# spot_check_rev_2.net
KiCad netlist of a schematic drawn in EAGLE
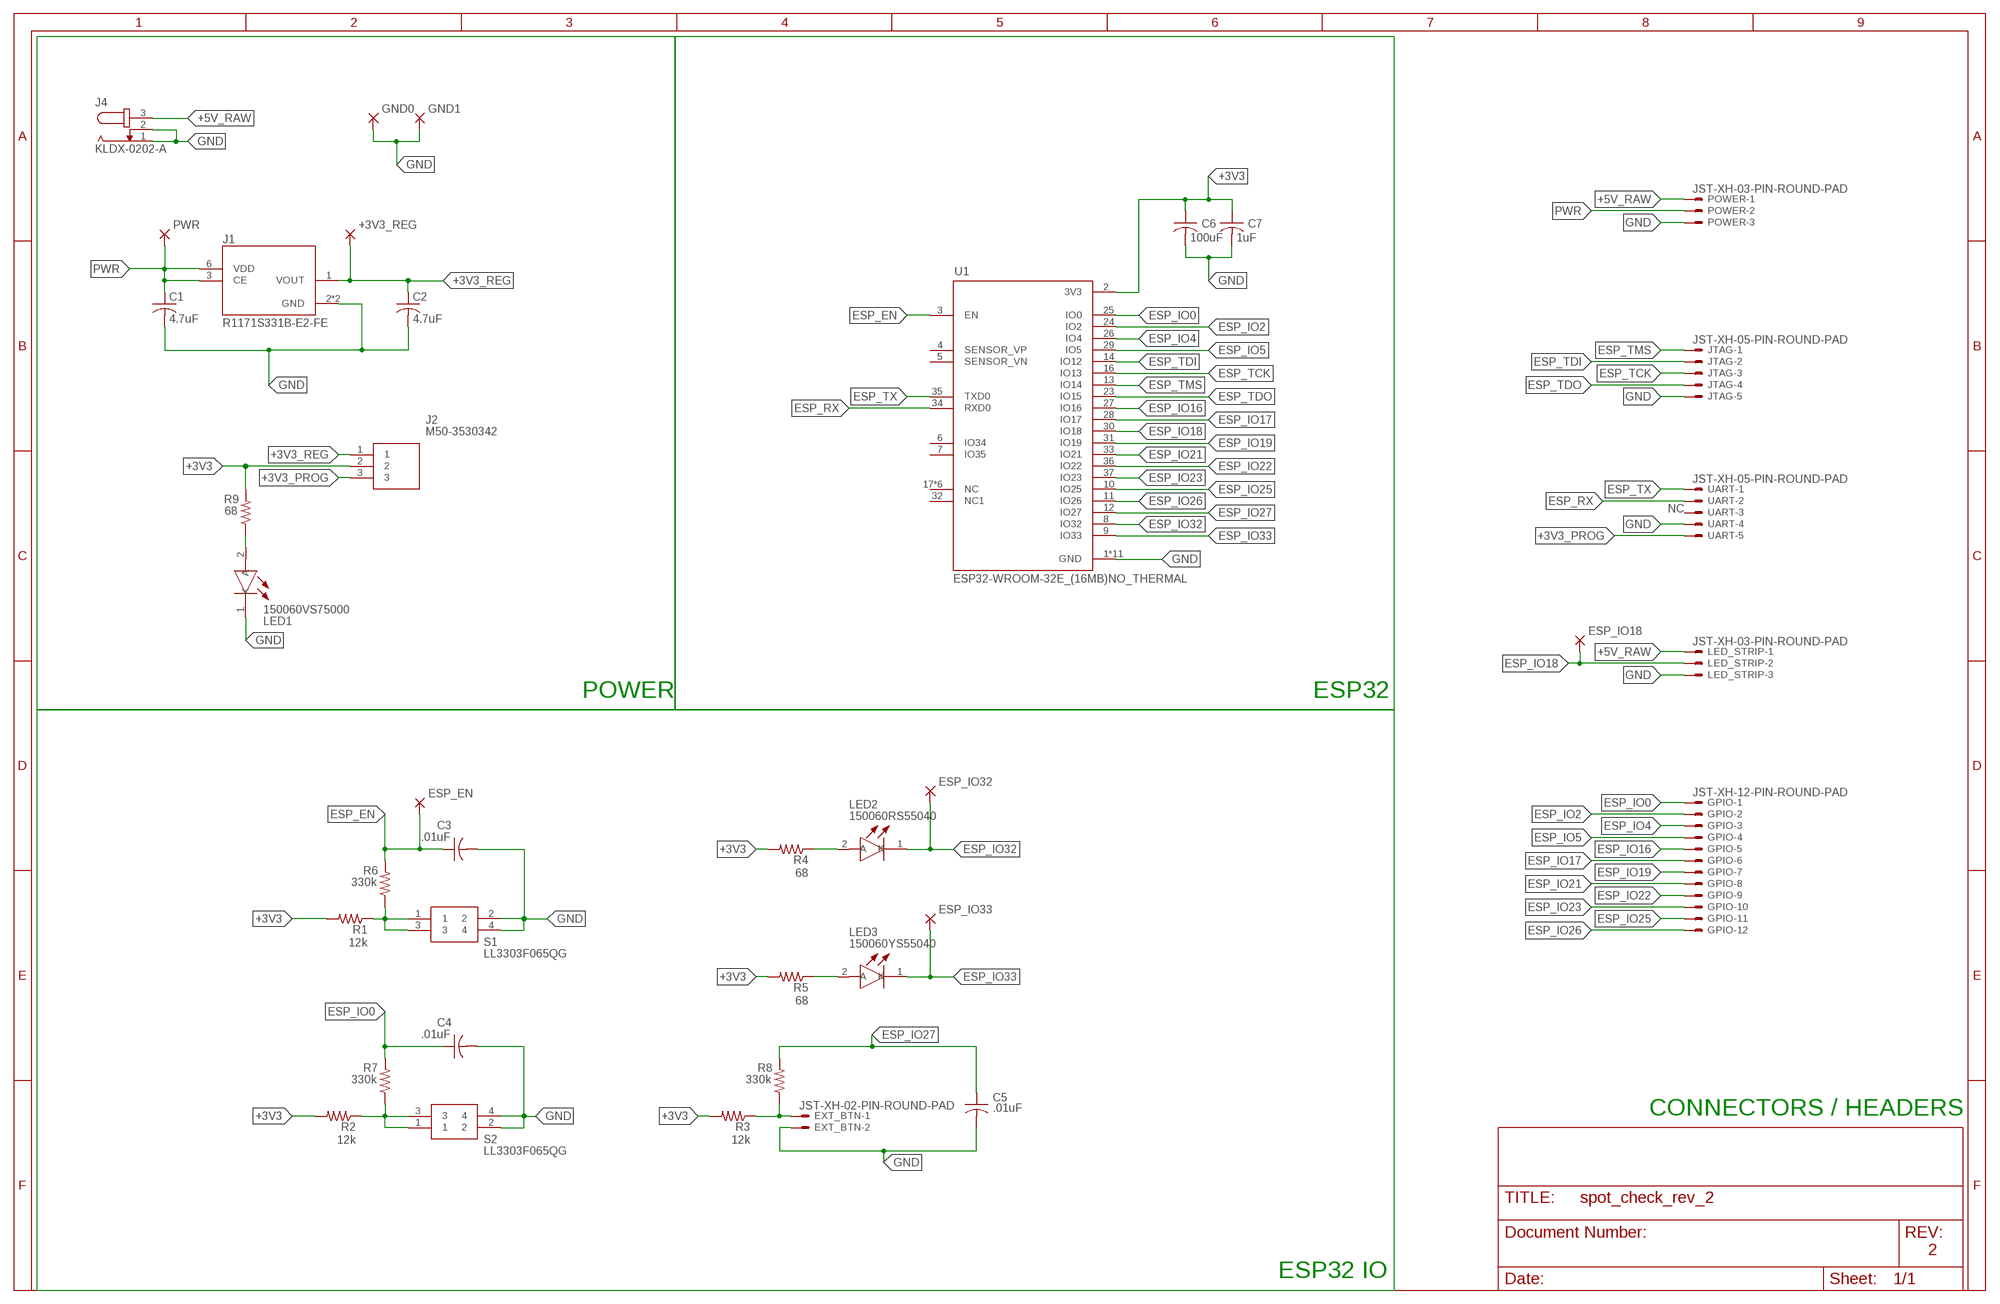
[diagram p0: schematic, sheet 1]

(export (version "E")
  (design (tool "Eeschema 10.0.6"))
  (components
    (comp (ref "+3V3_REG")
      (value "TP")
      (footprint "eagle-import:2,54_1,1")
      (libsource (lib "eagle-import") (part "2,54/1,1"))
    )
    (comp (ref "C1")
      (value "4.7uF")
      (footprint "eagle-import:C0805")
      (libsource (lib "eagle-import") (part "C-USC0805"))
    )
    (comp (ref "C2")
      (value "4.7uF")
      (footprint "eagle-import:C0805")
      (libsource (lib "eagle-import") (part "C-USC0805"))
    )
    (comp (ref "C3")
      (value ".01uF")
      (footprint "eagle-import:C0805")
      (libsource (lib "eagle-import") (part "C-USC0805"))
    )
    (comp (ref "C4")
      (value ".01uF")
      (footprint "eagle-import:C0805")
      (libsource (lib "eagle-import") (part "C-USC0805"))
    )
    (comp (ref "C5")
      (value ".01uF")
      (footprint "eagle-import:C0805")
      (libsource (lib "eagle-import") (part "C-USC0805"))
    )
    (comp (ref "C6")
      (value "100uF")
      (footprint "eagle-import:C0805")
      (libsource (lib "eagle-import") (part "C-USC0805"))
    )
    (comp (ref "C7")
      (value "1uF")
      (footprint "eagle-import:C0805")
      (libsource (lib "eagle-import") (part "C-USC0805"))
    )
    (comp (ref "ESP_EN")
      (value "TP")
      (footprint "eagle-import:2,54_1,1")
      (libsource (lib "eagle-import") (part "2,54/1,1"))
    )
    (comp (ref "ESP_IO18")
      (value "TP")
      (footprint "eagle-import:2,54_1,1")
      (libsource (lib "eagle-import") (part "2,54/1,1"))
    )
    (comp (ref "ESP_IO32")
      (value "TP")
      (footprint "eagle-import:2,54_1,1")
      (libsource (lib "eagle-import") (part "2,54/1,1"))
    )
    (comp (ref "ESP_IO33")
      (value "TP")
      (footprint "eagle-import:2,54_1,1")
      (libsource (lib "eagle-import") (part "2,54/1,1"))
    )
    (comp (ref "EXT_BTN")
      (value "JST-XH-02-PIN-ROUND-PAD")
      (footprint "eagle-import:JST-XH-02-PACKAGE-ROUND-PAD")
      (libsource (lib "eagle-import") (part "JST-XH-02-PIN-ROUND-PAD"))
    )
    (comp (ref "GND0")
      (value "TP")
      (footprint "eagle-import:2,54_1,1")
      (libsource (lib "eagle-import") (part "2,54/1,1"))
    )
    (comp (ref "GND1")
      (value "TP")
      (footprint "eagle-import:2,54_1,1")
      (libsource (lib "eagle-import") (part "2,54/1,1"))
    )
    (comp (ref "GPIO")
      (value "JST-XH-12-PIN-ROUND-PAD")
      (footprint "eagle-import:JST-XH-12-PACKAGE-ROUND-PAD")
      (libsource (lib "eagle-import") (part "JST-XH-12-PIN-ROUND-PAD"))
    )
    (comp (ref "J1")
      (value "R1171S331B-E2-FE")
      (footprint "eagle-import:REG_R1171S421B-E2-FE")
      (fields (field (name "MF") "Ricoh") (field (name "MP") "R1171S421B-E2-FE"))
      (libsource (lib "eagle-import") (part "R1171S421B-E2-FE"))
    )
    (comp (ref "J2")
      (value "M50-3530342")
      (footprint "eagle-import:HDRV3W40P0X127_1X3_381X210X430")
      (fields (field (name "MOUSER_PART_NUMBER") "855-M50-3530342"))
      (libsource (lib "eagle-import") (part "M50-3530342"))
    )
    (comp (ref "J4")
      (value "KLDX-0202-A")
      (footprint "eagle-import:SPC4077")
      (libsource (lib "eagle-import") (part "CONN-JACK"))
    )
    (comp (ref "JTAG")
      (value "JST-XH-05-PIN-ROUND-PAD")
      (footprint "eagle-import:JST-XH-05-PACKAGE-ROUND-PAD")
      (libsource (lib "eagle-import") (part "JST-XH-05-PIN-ROUND-PAD"))
    )
    (comp (ref "LED1")
      (value "150060VS75000")
      (footprint "eagle-import:LEDC1608X80N")
      (fields (field (name "MF") "Wurth Elektronik"))
      (libsource (lib "eagle-import") (part "150060VS75000"))
    )
    (comp (ref "LED2")
      (value "150060RS55040")
      (footprint "eagle-import:LEDC1608X80N")
      (fields (field (name "MF") "Wurth Elektronik") (field (name "MP") "150060VS75000"))
      (libsource (lib "eagle-import") (part "150060VS75000"))
    )
    (comp (ref "LED3")
      (value "150060YS55040")
      (footprint "eagle-import:LEDC1608X80N")
      (fields (field (name "MF") "Wurth Elektronik") (field (name "MP") "150060VS75000"))
      (libsource (lib "eagle-import") (part "150060VS75000"))
    )
    (comp (ref "LED_STRIP")
      (value "JST-XH-03-PIN-ROUND-PAD")
      (footprint "eagle-import:JST-XH-03-PACKAGE-ROUND-PAD")
      (libsource (lib "eagle-import") (part "JST-XH-03-PIN-ROUND-PAD"))
    )
    (comp (ref "POWER")
      (value "JST-XH-03-PIN-ROUND-PAD")
      (footprint "eagle-import:JST-XH-03-PACKAGE-ROUND-PAD")
      (libsource (lib "eagle-import") (part "JST-XH-03-PIN-ROUND-PAD"))
    )
    (comp (ref "PWR")
      (value "TP")
      (footprint "eagle-import:2,54_1,1")
      (libsource (lib "eagle-import") (part "2,54/1,1"))
    )
    (comp (ref "R1")
      (value "12k")
      (footprint "eagle-import:R0805")
      (libsource (lib "eagle-import") (part "R-US_R0805"))
    )
    (comp (ref "R2")
      (value "12k")
      (footprint "eagle-import:R0805")
      (libsource (lib "eagle-import") (part "R-US_R0805"))
    )
    (comp (ref "R3")
      (value "12k")
      (footprint "eagle-import:R0805")
      (libsource (lib "eagle-import") (part "R-US_R0805"))
    )
    (comp (ref "R4")
      (value "68")
      (footprint "eagle-import:R0805")
      (libsource (lib "eagle-import") (part "R-US_R0805"))
    )
    (comp (ref "R5")
      (value "68")
      (footprint "eagle-import:R0805")
      (libsource (lib "eagle-import") (part "R-US_R0805"))
    )
    (comp (ref "R6")
      (value "330k")
      (footprint "eagle-import:R0805")
      (libsource (lib "eagle-import") (part "R-US_R0805"))
    )
    (comp (ref "R7")
      (value "330k")
      (footprint "eagle-import:R0805")
      (libsource (lib "eagle-import") (part "R-US_R0805"))
    )
    (comp (ref "R8")
      (value "330k")
      (footprint "eagle-import:R0805")
      (libsource (lib "eagle-import") (part "R-US_R0805"))
    )
    (comp (ref "R9")
      (value "68")
      (footprint "eagle-import:R0805")
      (libsource (lib "eagle-import") (part "R-US_R0805"))
    )
    (comp (ref "S1")
      (value "LL3303F065QG")
      (footprint "eagle-import:LL3303F065QG")
      (fields (field (name "MOUSER_PART_NUMBER") "612-LL3303F065QG"))
      (libsource (lib "eagle-import") (part "LL3303F065QG"))
    )
    (comp (ref "S2")
      (value "LL3303F065QG")
      (footprint "eagle-import:LL3303F065QG")
      (fields (field (name "MOUSER_PART_NUMBER") "612-LL3303F065QG"))
      (libsource (lib "eagle-import") (part "LL3303F065QG"))
    )
    (comp (ref "U1")
      (value "ESP32-WROOM-32E_(16MB)NO_THERMAL")
      (footprint "eagle-import:MODULE_ESP32-WROOM-32E_(16MB)")
      (libsource (lib "eagle-import") (part "ESP32-WROOM-32E_(16MB)NO_THERMAL"))
    )
    (comp (ref "UART")
      (value "JST-XH-05-PIN-ROUND-PAD")
      (footprint "eagle-import:JST-XH-05-PACKAGE-ROUND-PAD")
      (fields (field (name "NC") "NC"))
      (libsource (lib "eagle-import") (part "JST-XH-05-PIN-ROUND-PAD"))
    )
  )
  (nets
    (net (code "1") (name "+3V3") (class "Default")
      (node (ref "C6") (pin "1") (pinfunction "1_1") (pintype "passive"))
      (node (ref "C7") (pin "1") (pinfunction "1_1") (pintype "passive"))
      (node (ref "J2") (pin "2") (pinfunction "2_2") (pintype "bidirectional"))
      (node (ref "R1") (pin "2") (pinfunction "2_2") (pintype "passive"))
      (node (ref "R2") (pin "2") (pinfunction "2_2") (pintype "passive"))
      (node (ref "R3") (pin "2") (pinfunction "2_2") (pintype "passive"))
      (node (ref "R4") (pin "2") (pinfunction "2_2") (pintype "passive"))
      (node (ref "R5") (pin "2") (pinfunction "2_2") (pintype "passive"))
      (node (ref "R9") (pin "2") (pinfunction "2_2") (pintype "passive"))
      (node (ref "U1") (pin "2") (pinfunction "3V3_2") (pintype "power_in"))
    )
    (net (code "2") (name "+3V3_PROG") (class "Default")
      (node (ref "J2") (pin "3") (pinfunction "3_3") (pintype "bidirectional"))
      (node (ref "UART") (pin "5") (pinfunction "S_5") (pintype "passive"))
    )
    (net (code "3") (name "+3V3_REG") (class "Default")
      (node (ref "+3V3_REG") (pin "1") (pinfunction "P_1") (pintype "passive"))
      (node (ref "C2") (pin "1") (pinfunction "1_1") (pintype "passive"))
      (node (ref "J1") (pin "1") (pinfunction "VOUT_1") (pintype "output"))
      (node (ref "J2") (pin "1") (pinfunction "1_1") (pintype "bidirectional"))
    )
    (net (code "4") (name "+5V_RAW") (class "Default")
      (node (ref "J4") (pin "3") (pinfunction "3_3") (pintype "passive"))
      (node (ref "LED_STRIP") (pin "1") (pinfunction "S_1") (pintype "passive"))
      (node (ref "POWER") (pin "1") (pinfunction "S_1") (pintype "passive"))
    )
    (net (code "5") (name "ESP_EN") (class "Default")
      (node (ref "C3") (pin "1") (pinfunction "1_1") (pintype "passive"))
      (node (ref "ESP_EN") (pin "1") (pinfunction "P_1") (pintype "passive"))
      (node (ref "R6") (pin "2") (pinfunction "2_2") (pintype "passive"))
      (node (ref "U1") (pin "3") (pinfunction "EN_3") (pintype "input"))
    )
    (net (code "6") (name "ESP_IO0") (class "Default")
      (node (ref "C4") (pin "1") (pinfunction "1_1") (pintype "passive"))
      (node (ref "GPIO") (pin "1") (pinfunction "S_1") (pintype "passive"))
      (node (ref "R7") (pin "2") (pinfunction "2_2") (pintype "passive"))
      (node (ref "U1") (pin "25") (pinfunction "IO0_25") (pintype "bidirectional"))
    )
    (net (code "7") (name "ESP_IO2") (class "Default")
      (node (ref "GPIO") (pin "2") (pinfunction "S_2") (pintype "passive"))
      (node (ref "U1") (pin "24") (pinfunction "IO2_24") (pintype "bidirectional"))
    )
    (net (code "8") (name "ESP_IO4") (class "Default")
      (node (ref "GPIO") (pin "3") (pinfunction "S_3") (pintype "passive"))
      (node (ref "U1") (pin "26") (pinfunction "IO4_26") (pintype "bidirectional"))
    )
    (net (code "9") (name "ESP_IO5") (class "Default")
      (node (ref "GPIO") (pin "4") (pinfunction "S_4") (pintype "passive"))
      (node (ref "U1") (pin "29") (pinfunction "IO5_29") (pintype "bidirectional"))
    )
    (net (code "10") (name "ESP_IO16") (class "Default")
      (node (ref "GPIO") (pin "5") (pinfunction "S_5") (pintype "passive"))
      (node (ref "U1") (pin "27") (pinfunction "IO16_27") (pintype "bidirectional"))
    )
    (net (code "11") (name "ESP_IO17") (class "Default")
      (node (ref "GPIO") (pin "6") (pinfunction "S_6") (pintype "passive"))
      (node (ref "U1") (pin "28") (pinfunction "IO17_28") (pintype "bidirectional"))
    )
    (net (code "12") (name "ESP_IO18") (class "Default")
      (node (ref "ESP_IO18") (pin "1") (pinfunction "P_1") (pintype "passive"))
      (node (ref "LED_STRIP") (pin "2") (pinfunction "S_2") (pintype "passive"))
      (node (ref "U1") (pin "30") (pinfunction "IO18_30") (pintype "bidirectional"))
    )
    (net (code "13") (name "ESP_IO19") (class "Default")
      (node (ref "GPIO") (pin "7") (pinfunction "S_7") (pintype "passive"))
      (node (ref "U1") (pin "31") (pinfunction "IO19_31") (pintype "bidirectional"))
    )
    (net (code "14") (name "ESP_IO21") (class "Default")
      (node (ref "GPIO") (pin "8") (pinfunction "S_8") (pintype "passive"))
      (node (ref "U1") (pin "33") (pinfunction "IO21_33") (pintype "bidirectional"))
    )
    (net (code "15") (name "ESP_IO22") (class "Default")
      (node (ref "GPIO") (pin "9") (pinfunction "S_9") (pintype "passive"))
      (node (ref "U1") (pin "36") (pinfunction "IO22_36") (pintype "bidirectional"))
    )
    (net (code "16") (name "ESP_IO23") (class "Default")
      (node (ref "GPIO") (pin "10") (pinfunction "S_10") (pintype "passive"))
      (node (ref "U1") (pin "37") (pinfunction "IO23_37") (pintype "bidirectional"))
    )
    (net (code "17") (name "ESP_IO25") (class "Default")
      (node (ref "GPIO") (pin "11") (pinfunction "S_11") (pintype "passive"))
      (node (ref "U1") (pin "10") (pinfunction "IO25_10") (pintype "bidirectional"))
    )
    (net (code "18") (name "ESP_IO26") (class "Default")
      (node (ref "GPIO") (pin "12") (pinfunction "S_12") (pintype "passive"))
      (node (ref "U1") (pin "11") (pinfunction "IO26_11") (pintype "bidirectional"))
    )
    (net (code "19") (name "ESP_IO27") (class "Default")
      (node (ref "C5") (pin "1") (pinfunction "1_1") (pintype "passive"))
      (node (ref "R8") (pin "2") (pinfunction "2_2") (pintype "passive"))
      (node (ref "U1") (pin "12") (pinfunction "IO27_12") (pintype "bidirectional"))
    )
    (net (code "20") (name "ESP_IO32") (class "Default")
      (node (ref "ESP_IO32") (pin "1") (pinfunction "P_1") (pintype "passive"))
      (node (ref "LED2") (pin "1") (pinfunction "K_1") (pintype "bidirectional"))
      (node (ref "U1") (pin "8") (pinfunction "IO32_8") (pintype "bidirectional"))
    )
    (net (code "21") (name "ESP_IO33") (class "Default")
      (node (ref "ESP_IO33") (pin "1") (pinfunction "P_1") (pintype "passive"))
      (node (ref "LED3") (pin "1") (pinfunction "K_1") (pintype "bidirectional"))
      (node (ref "U1") (pin "9") (pinfunction "IO33_9") (pintype "bidirectional"))
    )
    (net (code "22") (name "ESP_RX") (class "Default")
      (node (ref "U1") (pin "34") (pinfunction "RXD0_34") (pintype "bidirectional"))
      (node (ref "UART") (pin "2") (pinfunction "S_2") (pintype "passive"))
    )
    (net (code "23") (name "ESP_TCK") (class "Default")
      (node (ref "JTAG") (pin "3") (pinfunction "S_3") (pintype "passive"))
      (node (ref "U1") (pin "16") (pinfunction "IO13_16") (pintype "bidirectional"))
    )
    (net (code "24") (name "ESP_TDI") (class "Default")
      (node (ref "JTAG") (pin "2") (pinfunction "S_2") (pintype "passive"))
      (node (ref "U1") (pin "14") (pinfunction "IO12_14") (pintype "bidirectional"))
    )
    (net (code "25") (name "ESP_TDO") (class "Default")
      (node (ref "JTAG") (pin "4") (pinfunction "S_4") (pintype "passive"))
      (node (ref "U1") (pin "23") (pinfunction "IO15_23") (pintype "bidirectional"))
    )
    (net (code "26") (name "ESP_TMS") (class "Default")
      (node (ref "JTAG") (pin "1") (pinfunction "S_1") (pintype "passive"))
      (node (ref "U1") (pin "13") (pinfunction "IO14_13") (pintype "bidirectional"))
    )
    (net (code "27") (name "ESP_TX") (class "Default")
      (node (ref "U1") (pin "35") (pinfunction "TXD0_35") (pintype "bidirectional"))
      (node (ref "UART") (pin "1") (pinfunction "S_1") (pintype "passive"))
    )
    (net (code "28") (name "GND") (class "Default")
      (node (ref "C1") (pin "2") (pinfunction "2_2") (pintype "passive"))
      (node (ref "C2") (pin "2") (pinfunction "2_2") (pintype "passive"))
      (node (ref "C3") (pin "2") (pinfunction "2_2") (pintype "passive"))
      (node (ref "C4") (pin "2") (pinfunction "2_2") (pintype "passive"))
      (node (ref "C5") (pin "2") (pinfunction "2_2") (pintype "passive"))
      (node (ref "C6") (pin "2") (pinfunction "2_2") (pintype "passive"))
      (node (ref "C7") (pin "2") (pinfunction "2_2") (pintype "passive"))
      (node (ref "EXT_BTN") (pin "2") (pinfunction "S_2") (pintype "passive"))
      (node (ref "GND0") (pin "1") (pinfunction "P_1") (pintype "passive"))
      (node (ref "GND1") (pin "1") (pinfunction "P_1") (pintype "passive"))
      (node (ref "J1") (pin "2") (pinfunction "GND_2") (pintype "power_in"))
      (node (ref "J1") (pin "5") (pinfunction "GND_5") (pintype "power_in"))
      (node (ref "J4") (pin "1") (pinfunction "1_1") (pintype "passive"))
      (node (ref "J4") (pin "2") (pinfunction "2_2") (pintype "passive"))
      (node (ref "JTAG") (pin "5") (pinfunction "S_5") (pintype "passive"))
      (node (ref "LED1") (pin "1") (pinfunction "K_1") (pintype "bidirectional"))
      (node (ref "LED_STRIP") (pin "3") (pinfunction "S_3") (pintype "passive"))
      (node (ref "POWER") (pin "3") (pinfunction "S_3") (pintype "passive"))
      (node (ref "S1") (pin "2") (pinfunction "2_2") (pintype "bidirectional"))
      (node (ref "S1") (pin "4") (pinfunction "4_4") (pintype "bidirectional"))
      (node (ref "S2") (pin "2") (pinfunction "2_2") (pintype "bidirectional"))
      (node (ref "S2") (pin "4") (pinfunction "4_4") (pintype "bidirectional"))
      (node (ref "U1") (pin "1") (pinfunction "GND_1") (pintype "power_in"))
      (node (ref "U1") (pin "15") (pinfunction "GND_15") (pintype "power_in"))
      (node (ref "U1") (pin "38") (pinfunction "GND_38") (pintype "power_in"))
      (node (ref "U1") (pin "39_1") (pinfunction "GND_39_1") (pintype "power_in"))
      (node (ref "U1") (pin "39_13") (pinfunction "GND_39_13") (pintype "power_in"))
      (node (ref "U1") (pin "39_18") (pinfunction "GND_39_18") (pintype "power_in"))
      (node (ref "U1") (pin "39_3") (pinfunction "GND_39_3") (pintype "power_in"))
      (node (ref "U1") (pin "39_4") (pinfunction "GND_39_4") (pintype "power_in"))
      (node (ref "U1") (pin "39_6") (pinfunction "GND_39_6") (pintype "power_in"))
      (node (ref "U1") (pin "39_7") (pinfunction "GND_39_7") (pintype "power_in"))
      (node (ref "U1") (pin "39_9") (pinfunction "GND_39_9") (pintype "power_in"))
      (node (ref "UART") (pin "4") (pinfunction "S_4") (pintype "passive"))
    )
    (net (code "29") (name "Net-(EXT_BTNA-S)") (class "Default")
      (node (ref "EXT_BTN") (pin "1") (pinfunction "S_1") (pintype "passive"))
      (node (ref "R3") (pin "1") (pinfunction "1_1") (pintype "passive"))
      (node (ref "R8") (pin "1") (pinfunction "1_1") (pintype "passive"))
    )
    (net (code "30") (name "Net-(LED1-A)") (class "Default")
      (node (ref "LED1") (pin "2") (pinfunction "A_2") (pintype "bidirectional"))
      (node (ref "R9") (pin "1") (pinfunction "1_1") (pintype "passive"))
    )
    (net (code "31") (name "Net-(LED2-A)") (class "Default")
      (node (ref "LED2") (pin "2") (pinfunction "A_2") (pintype "bidirectional"))
      (node (ref "R4") (pin "1") (pinfunction "1_1") (pintype "passive"))
    )
    (net (code "32") (name "Net-(LED3-A)") (class "Default")
      (node (ref "LED3") (pin "2") (pinfunction "A_2") (pintype "bidirectional"))
      (node (ref "R5") (pin "1") (pinfunction "1_1") (pintype "passive"))
    )
    (net (code "33") (name "Net-(R1-Pad1)") (class "Default")
      (node (ref "R1") (pin "1") (pinfunction "1_1") (pintype "passive"))
      (node (ref "R6") (pin "1") (pinfunction "1_1") (pintype "passive"))
      (node (ref "S1") (pin "1") (pinfunction "1_1") (pintype "bidirectional"))
      (node (ref "S1") (pin "3") (pinfunction "3_3") (pintype "bidirectional"))
    )
    (net (code "34") (name "Net-(R2-Pad1)") (class "Default")
      (node (ref "R2") (pin "1") (pinfunction "1_1") (pintype "passive"))
      (node (ref "R7") (pin "1") (pinfunction "1_1") (pintype "passive"))
      (node (ref "S2") (pin "1") (pinfunction "1_1") (pintype "bidirectional"))
      (node (ref "S2") (pin "3") (pinfunction "3_3") (pintype "bidirectional"))
    )
    (net (code "35") (name "PWR") (class "Default")
      (node (ref "C1") (pin "1") (pinfunction "1_1") (pintype "passive"))
      (node (ref "J1") (pin "3") (pinfunction "CE_3") (pintype "input"))
      (node (ref "J1") (pin "6") (pinfunction "VDD_6") (pintype "input"))
      (node (ref "POWER") (pin "2") (pinfunction "S_2") (pintype "passive"))
      (node (ref "PWR") (pin "1") (pinfunction "P_1") (pintype "passive"))
    )
    (net (code "36") (name "unconnected-(U1-IO34-Pad6)") (class "Default")
      (node (ref "U1") (pin "6") (pinfunction "IO34_6") (pintype "input"))
    )
    (net (code "37") (name "unconnected-(U1-IO35-Pad7)") (class "Default")
      (node (ref "U1") (pin "7") (pinfunction "IO35_7") (pintype "input"))
    )
    (net (code "38") (name "unconnected-(U1-NC-Pad17)") (class "Default")
      (node (ref "U1") (pin "17") (pinfunction "NC_17") (pintype "no_connect"))
    )
    (net (code "39") (name "unconnected-(U1-NC-Pad18)") (class "Default")
      (node (ref "U1") (pin "18") (pinfunction "NC_18") (pintype "no_connect"))
    )
    (net (code "40") (name "unconnected-(U1-NC-Pad19)") (class "Default")
      (node (ref "U1") (pin "19") (pinfunction "NC_19") (pintype "no_connect"))
    )
    (net (code "41") (name "unconnected-(U1-NC-Pad20)") (class "Default")
      (node (ref "U1") (pin "20") (pinfunction "NC_20") (pintype "no_connect"))
    )
    (net (code "42") (name "unconnected-(U1-NC-Pad21)") (class "Default")
      (node (ref "U1") (pin "21") (pinfunction "NC_21") (pintype "no_connect"))
    )
    (net (code "43") (name "unconnected-(U1-NC-Pad22)") (class "Default")
      (node (ref "U1") (pin "22") (pinfunction "NC_22") (pintype "no_connect"))
    )
    (net (code "44") (name "unconnected-(U1-NC1-Pad32)") (class "Default")
      (node (ref "U1") (pin "32") (pinfunction "NC1_32") (pintype "no_connect"))
    )
    (net (code "45") (name "unconnected-(U1-SENSOR_VN-Pad5)") (class "Default")
      (node (ref "U1") (pin "5") (pinfunction "SENSOR_VN_5") (pintype "input"))
    )
    (net (code "46") (name "unconnected-(U1-SENSOR_VP-Pad4)") (class "Default")
      (node (ref "U1") (pin "4") (pinfunction "SENSOR_VP_4") (pintype "input"))
    )
    (net (code "47") (name "unconnected-(UARTC-S-Pad3)") (class "Default")
      (node (ref "UART") (pin "3") (pinfunction "S_3") (pintype "passive"))
    )
  )
)
